# Driver.net
KiCad netlist of a schematic drawn in Altium Designer
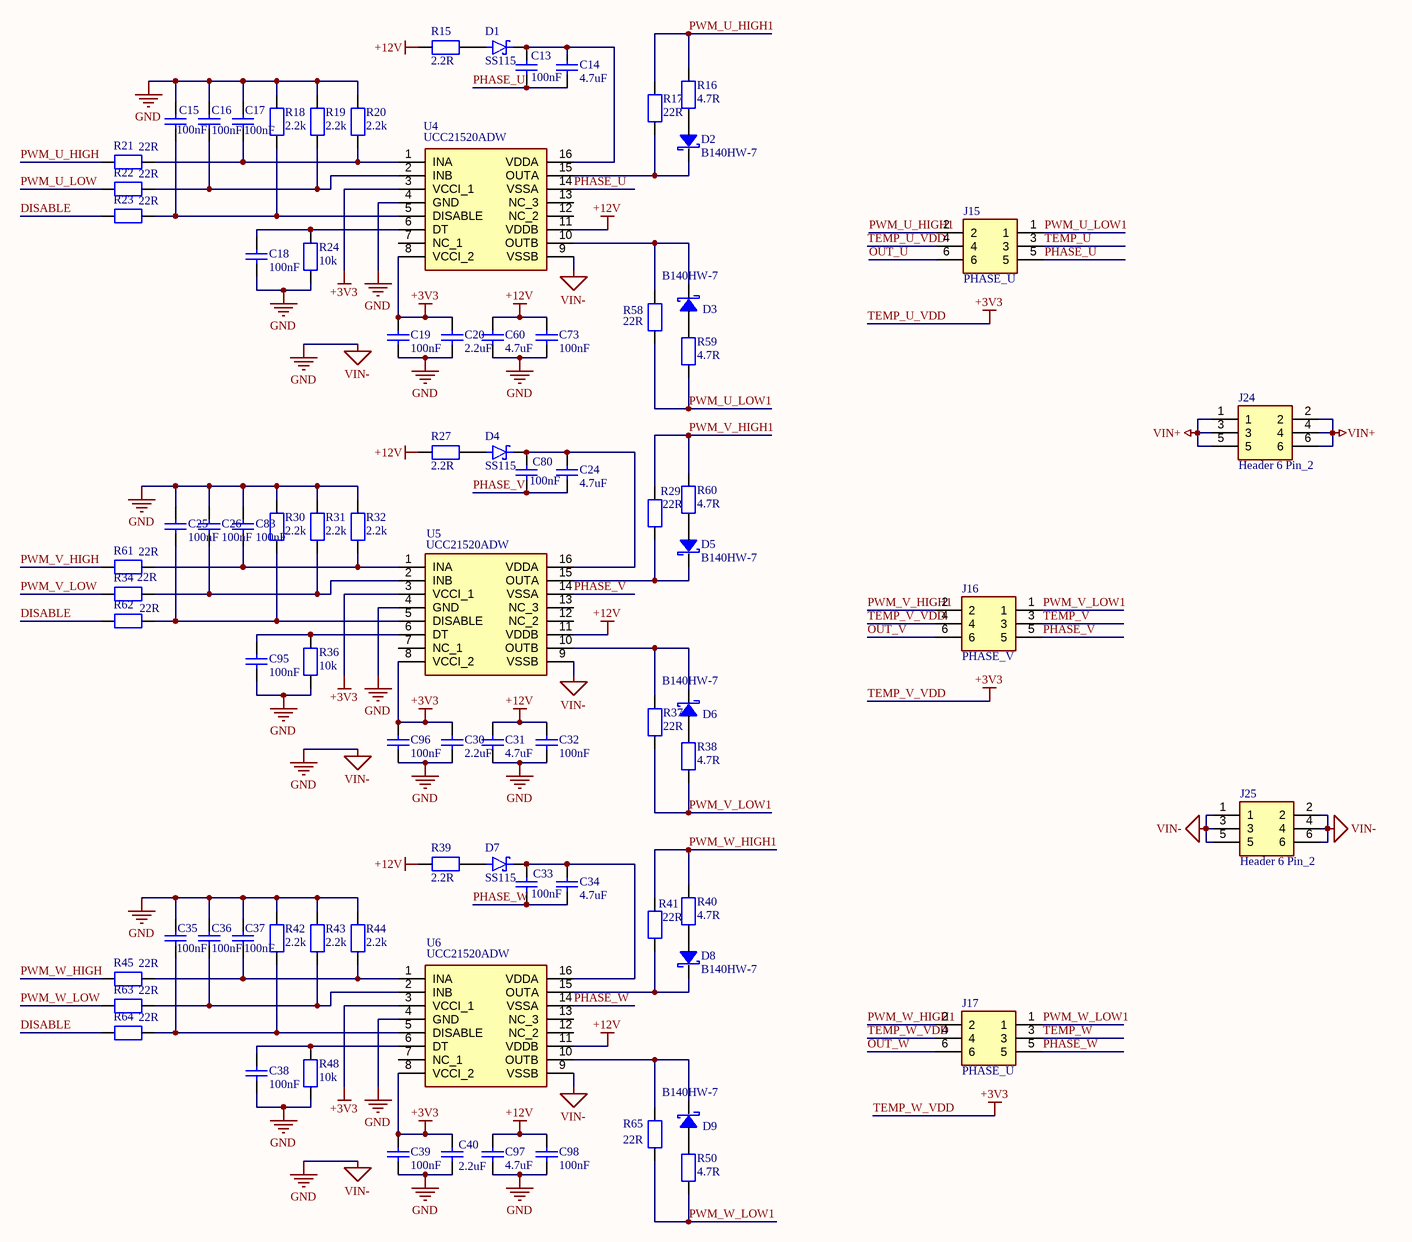
[diagram p0: Driver.SchDoc]

(export (version "E")
  (design (tool "Eeschema 10.0.6"))
  (components
    (comp (ref "C13")
      (value "100nF")
      (footprint "C0603")
      (description "100nF ± 10% 50V")
      (fields
        (field (name "MANUFACTURER") "Yageo")
        (field (name "MANUFACTURER PART NUMBER") "CS0603KRX7R9BB104")
      )
      (libsource (lib "VESC_MotorController") (part "100nF ± 10% 50V"))
    )
    (comp (ref "C14")
      (value "4.7uF")
      (footprint "C0603")
      (description "4.7uF ± 10% 50V")
      (fields
        (field (name "MANUFACTURER") "Yageo")
        (field (name "MANUFACTURER PART NUMBER") "GRM188R61H225ME11J")
      )
      (libsource (lib "VESC_MotorController") (part "4.7uF ± 10% 50V"))
    )
    (comp (ref "C15")
      (value "100nF")
      (footprint "C0603")
      (description "100nF ± 10% 50V")
      (fields
        (field (name "MANUFACTURER") "Yageo")
        (field (name "MANUFACTURER PART NUMBER") "CS0603KRX7R9BB104")
      )
      (libsource (lib "VESC_MotorController") (part "100nF ± 10% 50V"))
    )
    (comp (ref "C16")
      (value "100nF")
      (footprint "C0603")
      (description "100nF ± 10% 50V")
      (fields
        (field (name "MANUFACTURER") "Yageo")
        (field (name "MANUFACTURER PART NUMBER") "CS0603KRX7R9BB104")
      )
      (libsource (lib "VESC_MotorController") (part "100nF ± 10% 50V"))
    )
    (comp (ref "C17")
      (value "100nF")
      (footprint "C0603")
      (description "100nF ± 10% 50V")
      (fields
        (field (name "MANUFACTURER") "Yageo")
        (field (name "MANUFACTURER PART NUMBER") "CS0603KRX7R9BB104")
      )
      (libsource (lib "VESC_MotorController") (part "100nF ± 10% 50V"))
    )
    (comp (ref "C18")
      (value "100nF")
      (footprint "C0603")
      (description "100nF ± 10% 50V")
      (fields
        (field (name "MANUFACTURER") "Yageo")
        (field (name "MANUFACTURER PART NUMBER") "CS0603KRX7R9BB104")
      )
      (libsource (lib "VESC_MotorController") (part "100nF ± 10% 50V"))
    )
    (comp (ref "C19")
      (value "100nF")
      (footprint "C0603")
      (description "100nF ± 10% 50V")
      (fields
        (field (name "MANUFACTURER") "Yageo")
        (field (name "MANUFACTURER PART NUMBER") "CS0603KRX7R9BB104")
      )
      (libsource (lib "VESC_MotorController") (part "100nF ± 10% 50V"))
    )
    (comp (ref "C20")
      (value "2.2uF")
      (footprint "C0603")
      (description "2.2uF ± 10% 50V")
      (fields
        (field (name "MANUFACTURER") "Yageo")
        (field (name "MANUFACTURER PART NUMBER") "GRM188R61H225ME11J")
      )
      (libsource (lib "VESC_MotorController") (part "2.2uF ± 10% 50V"))
    )
    (comp (ref "C24")
      (value "4.7uF")
      (footprint "C0603")
      (description "4.7uF ± 10% 50V")
      (fields
        (field (name "MANUFACTURER") "Yageo")
        (field (name "MANUFACTURER PART NUMBER") "GRM188R61H225ME11J")
      )
      (libsource (lib "VESC_MotorController") (part "4.7uF ± 10% 50V"))
    )
    (comp (ref "C25")
      (value "100nF")
      (footprint "C0603")
      (description "100nF ± 10% 50V")
      (fields
        (field (name "MANUFACTURER") "Yageo")
        (field (name "MANUFACTURER PART NUMBER") "CS0603KRX7R9BB104")
      )
      (libsource (lib "VESC_MotorController") (part "100nF ± 10% 50V"))
    )
    (comp (ref "C26")
      (value "100nF")
      (footprint "C0603")
      (description "100nF ± 10% 50V")
      (fields
        (field (name "MANUFACTURER") "Yageo")
        (field (name "MANUFACTURER PART NUMBER") "CS0603KRX7R9BB104")
      )
      (libsource (lib "VESC_MotorController") (part "100nF ± 10% 50V"))
    )
    (comp (ref "C30")
      (value "2.2uF")
      (footprint "C0603")
      (description "2.2uF ± 10% 50V")
      (fields
        (field (name "MANUFACTURER") "Yageo")
        (field (name "MANUFACTURER PART NUMBER") "GRM188R61H225ME11J")
      )
      (libsource (lib "VESC_MotorController") (part "2.2uF ± 10% 50V"))
    )
    (comp (ref "C31")
      (value "4.7uF")
      (footprint "C0603")
      (description "4.7uF ± 10% 50V")
      (fields
        (field (name "MANUFACTURER") "Yageo")
        (field (name "MANUFACTURER PART NUMBER") "GRM188R61H225ME11J")
      )
      (libsource (lib "VESC_MotorController") (part "4.7uF ± 10% 50V"))
    )
    (comp (ref "C32")
      (value "100nF")
      (footprint "C0603")
      (description "100nF ± 10% 50V")
      (fields
        (field (name "MANUFACTURER") "Yageo")
        (field (name "MANUFACTURER PART NUMBER") "CS0603KRX7R9BB104")
      )
      (libsource (lib "VESC_MotorController") (part "100nF ± 10% 50V"))
    )
    (comp (ref "C33")
      (value "100nF")
      (footprint "C0603")
      (description "100nF ± 10% 50V")
      (fields
        (field (name "MANUFACTURER") "Yageo")
        (field (name "MANUFACTURER PART NUMBER") "CS0603KRX7R9BB104")
      )
      (libsource (lib "VESC_MotorController") (part "100nF ± 10% 50V"))
    )
    (comp (ref "C34")
      (value "4.7uF")
      (footprint "C0603")
      (description "4.7uF ± 10% 50V")
      (fields
        (field (name "MANUFACTURER") "Yageo")
        (field (name "MANUFACTURER PART NUMBER") "GRM188R61H225ME11J")
      )
      (libsource (lib "VESC_MotorController") (part "4.7uF ± 10% 50V"))
    )
    (comp (ref "C35")
      (value "100nF")
      (footprint "C0603")
      (description "100nF ± 10% 50V")
      (fields
        (field (name "MANUFACTURER") "Yageo")
        (field (name "MANUFACTURER PART NUMBER") "CS0603KRX7R9BB104")
      )
      (libsource (lib "VESC_MotorController") (part "100nF ± 10% 50V"))
    )
    (comp (ref "C36")
      (value "100nF")
      (footprint "C0603")
      (description "100nF ± 10% 50V")
      (fields
        (field (name "MANUFACTURER") "Yageo")
        (field (name "MANUFACTURER PART NUMBER") "CS0603KRX7R9BB104")
      )
      (libsource (lib "VESC_MotorController") (part "100nF ± 10% 50V"))
    )
    (comp (ref "C37")
      (value "100nF")
      (footprint "C0603")
      (description "100nF ± 10% 50V")
      (fields
        (field (name "MANUFACTURER") "Yageo")
        (field (name "MANUFACTURER PART NUMBER") "CS0603KRX7R9BB104")
      )
      (libsource (lib "VESC_MotorController") (part "100nF ± 10% 50V"))
    )
    (comp (ref "C38")
      (value "100nF")
      (footprint "C0603")
      (description "100nF ± 10% 50V")
      (fields
        (field (name "MANUFACTURER") "Yageo")
        (field (name "MANUFACTURER PART NUMBER") "CS0603KRX7R9BB104")
      )
      (libsource (lib "VESC_MotorController") (part "100nF ± 10% 50V"))
    )
    (comp (ref "C39")
      (value "100nF")
      (footprint "C0603")
      (description "100nF ± 10% 50V")
      (fields
        (field (name "MANUFACTURER") "Yageo")
        (field (name "MANUFACTURER PART NUMBER") "CS0603KRX7R9BB104")
      )
      (libsource (lib "VESC_MotorController") (part "100nF ± 10% 50V"))
    )
    (comp (ref "C40")
      (value "2.2uF")
      (footprint "C0603")
      (description "2.2uF ± 10% 50V")
      (fields
        (field (name "MANUFACTURER") "Yageo")
        (field (name "MANUFACTURER PART NUMBER") "GRM188R61H225ME11J")
      )
      (libsource (lib "VESC_MotorController") (part "2.2uF ± 10% 50V"))
    )
    (comp (ref "C60")
      (value "4.7uF")
      (footprint "C0603")
      (description "4.7uF ± 10% 50V")
      (fields
        (field (name "MANUFACTURER") "Yageo")
        (field (name "MANUFACTURER PART NUMBER") "GRM188R61H225ME11J")
      )
      (libsource (lib "VESC_MotorController") (part "4.7uF ± 10% 50V"))
    )
    (comp (ref "C73")
      (value "100nF")
      (footprint "C0603")
      (description "100nF ± 10% 50V")
      (fields
        (field (name "MANUFACTURER") "Yageo")
        (field (name "MANUFACTURER PART NUMBER") "CS0603KRX7R9BB104")
      )
      (libsource (lib "VESC_MotorController") (part "100nF ± 10% 50V"))
    )
    (comp (ref "C80")
      (value "100nF")
      (footprint "C0603")
      (description "100nF ± 10% 50V")
      (fields
        (field (name "MANUFACTURER") "Yageo")
        (field (name "MANUFACTURER PART NUMBER") "CS0603KRX7R9BB104")
      )
      (libsource (lib "VESC_MotorController") (part "100nF ± 10% 50V"))
    )
    (comp (ref "C83")
      (value "100nF")
      (footprint "C0603")
      (description "100nF ± 10% 50V")
      (fields
        (field (name "MANUFACTURER") "Yageo")
        (field (name "MANUFACTURER PART NUMBER") "CS0603KRX7R9BB104")
      )
      (libsource (lib "VESC_MotorController") (part "100nF ± 10% 50V"))
    )
    (comp (ref "C95")
      (value "100nF")
      (footprint "C0603")
      (description "100nF ± 10% 50V")
      (fields
        (field (name "MANUFACTURER") "Yageo")
        (field (name "MANUFACTURER PART NUMBER") "CS0603KRX7R9BB104")
      )
      (libsource (lib "VESC_MotorController") (part "100nF ± 10% 50V"))
    )
    (comp (ref "C96")
      (value "100nF")
      (footprint "C0603")
      (description "100nF ± 10% 50V")
      (fields
        (field (name "MANUFACTURER") "Yageo")
        (field (name "MANUFACTURER PART NUMBER") "CS0603KRX7R9BB104")
      )
      (libsource (lib "VESC_MotorController") (part "100nF ± 10% 50V"))
    )
    (comp (ref "C97")
      (value "4.7uF")
      (footprint "C0603")
      (description "4.7uF ± 10% 50V")
      (fields
        (field (name "MANUFACTURER") "Yageo")
        (field (name "MANUFACTURER PART NUMBER") "GRM188R61H225ME11J")
      )
      (libsource (lib "VESC_MotorController") (part "4.7uF ± 10% 50V"))
    )
    (comp (ref "C98")
      (value "100nF")
      (footprint "C0603")
      (description "100nF ± 10% 50V")
      (fields
        (field (name "MANUFACTURER") "Yageo")
        (field (name "MANUFACTURER PART NUMBER") "CS0603KRX7R9BB104")
      )
      (libsource (lib "VESC_MotorController") (part "100nF ± 10% 50V"))
    )
    (comp (ref "D1")
      (value "SS115")
      (footprint "DIOM4325X250N")
      (description "Schottky Diodes & Rectifiers 1A, 150V, Schottky Rectifier")
      (fields (field (name "MANUFACTURER") "Taiwan Semiconductor"))
      (libsource (lib "VESC_MotorController") (part "SS115"))
    )
    (comp (ref "D2")
      (value "B140HW-7")
      (footprint "SOD123")
      (description "Schottky Diodes & Rectifiers 1A, 40V")
      (fields (field (name "MANUFACTURER") "Diodes"))
      (libsource (lib "VESC_MotorController") (part "B140HW-7"))
    )
    (comp (ref "D3")
      (value "B140HW-7")
      (footprint "SOD123")
      (description "Schottky Diodes & Rectifiers 1A, 40V")
      (fields (field (name "MANUFACTURER") "Diodes"))
      (libsource (lib "VESC_MotorController") (part "B140HW-7"))
    )
    (comp (ref "D4")
      (value "SS115")
      (footprint "DIOM4325X250N")
      (description "Schottky Diodes & Rectifiers 1A, 150V, Schottky Rectifier")
      (fields (field (name "MANUFACTURER") "Taiwan Semiconductor"))
      (libsource (lib "VESC_MotorController") (part "SS115"))
    )
    (comp (ref "D5")
      (value "B140HW-7")
      (footprint "SOD123")
      (description "Schottky Diodes & Rectifiers 1A, 40V")
      (fields (field (name "MANUFACTURER") "Diodes"))
      (libsource (lib "VESC_MotorController") (part "B140HW-7"))
    )
    (comp (ref "D6")
      (value "B140HW-7")
      (footprint "SOD123")
      (description "Schottky Diodes & Rectifiers 1A, 40V")
      (fields (field (name "MANUFACTURER") "Diodes"))
      (libsource (lib "VESC_MotorController") (part "B140HW-7"))
    )
    (comp (ref "D7")
      (value "SS115")
      (footprint "DIOM4325X250N")
      (description "Schottky Diodes & Rectifiers 1A, 150V, Schottky Rectifier")
      (fields (field (name "MANUFACTURER") "Taiwan Semiconductor"))
      (libsource (lib "VESC_MotorController") (part "SS115"))
    )
    (comp (ref "D8")
      (value "B140HW-7")
      (footprint "SOD123")
      (description "Schottky Diodes & Rectifiers 1A, 40V")
      (fields (field (name "MANUFACTURER") "Diodes"))
      (libsource (lib "VESC_MotorController") (part "B140HW-7"))
    )
    (comp (ref "D9")
      (value "B140HW-7")
      (footprint "SOD123")
      (description "Schottky Diodes & Rectifiers 1A, 40V")
      (fields (field (name "MANUFACTURER") "Diodes"))
      (libsource (lib "VESC_MotorController") (part "B140HW-7"))
    )
    (comp (ref "J15")
      (value "PHASE_U")
      (footprint "61300621121")
      (fields
        (field (name "MANUFACTURER") "Wurth Elektronik")
        (field (name "MANUFACTURER PART NUMBER") "61300621121")
      )
      (libsource (lib "") (part "Header 6 Pin_2_1"))
    )
    (comp (ref "J16")
      (value "PHASE_V")
      (footprint "61300621121")
      (fields
        (field (name "MANUFACTURER") "Wurth Elektronik")
        (field (name "MANUFACTURER PART NUMBER") "61300621121")
      )
      (libsource (lib "") (part "Header 6 Pin_2_1"))
    )
    (comp (ref "J17")
      (value "PHASE_U")
      (footprint "61300621121")
      (fields
        (field (name "MANUFACTURER") "Wurth Elektronik")
        (field (name "MANUFACTURER PART NUMBER") "61300621121")
      )
      (libsource (lib "") (part "Header 6 Pin_2_1"))
    )
    (comp (ref "J24")
      (value "Header 6 Pin_2")
      (footprint "61300621121")
      (fields
        (field (name "MANUFACTURER") "Wurth Elektronik")
        (field (name "MANUFACTURER PART NUMBER") "61300621121")
      )
      (libsource (lib "VESC_MotorController") (part "Header 6 Pin_2"))
    )
    (comp (ref "J25")
      (value "Header 6 Pin_2")
      (footprint "61300621121")
      (fields
        (field (name "MANUFACTURER") "Wurth Elektronik")
        (field (name "MANUFACTURER PART NUMBER") "61300621121")
      )
      (libsource (lib "VESC_MotorController") (part "Header 6 Pin_2"))
    )
    (comp (ref "R15")
      (value "2.2R")
      (footprint "R0603")
      (description "2.2 ohm 0.1W ±1%")
      (fields
        (field (name "MANUFACTURER PART NUMBER") "RC0603FR-072R2L")
        (field (name "MANUFACTURER") "Yageo")
      )
      (libsource (lib "VESC_MotorController") (part "2.2ohm 0.1W ±1%"))
    )
    (comp (ref "R16")
      (value "4.7R")
      (footprint "R0603")
      (description "4.7 ohm 0.1W ±1%")
      (fields
        (field (name "MANUFACTURER PART NUMBER") "RC1206FR-074R7L")
        (field (name "MANUFACTURER") "Yageo")
      )
      (libsource (lib "VESC_MotorController") (part "4.7ohm 0.1W ±10%"))
    )
    (comp (ref "R17")
      (value "22R")
      (footprint "R0603")
      (description "22 ohm 0.1W ±1%")
      (fields
        (field (name "MANUFACTURER PART NUMBER") "RC0603FR-0722RL")
        (field (name "MANUFACTURER") "Yageo")
      )
      (libsource (lib "VESC_MotorController") (part "22ohm 0.1W ±1%"))
    )
    (comp (ref "R18")
      (value "2.2k")
      (footprint "R0603")
      (description "2.2 kOhms ±1% 0.1W")
      (fields
        (field (name "MANUFACTURER") "Yageo")
        (field (name "MANUFACTURER PART NUMBER") "RC0603FR-072K2L")
      )
      (libsource (lib "VESC_MotorController") (part "2.2 kOhms ±1% 0.1W"))
    )
    (comp (ref "R19")
      (value "2.2k")
      (footprint "R0603")
      (description "2.2 kOhms ±1% 0.1W")
      (fields
        (field (name "MANUFACTURER") "Yageo")
        (field (name "MANUFACTURER PART NUMBER") "RC0603FR-072K2L")
      )
      (libsource (lib "VESC_MotorController") (part "2.2 kOhms ±1% 0.1W"))
    )
    (comp (ref "R20")
      (value "2.2k")
      (footprint "R0603")
      (description "2.2 kOhms ±1% 0.1W")
      (fields
        (field (name "MANUFACTURER") "Yageo")
        (field (name "MANUFACTURER PART NUMBER") "RC0603FR-072K2L")
      )
      (libsource (lib "VESC_MotorController") (part "2.2 kOhms ±1% 0.1W"))
    )
    (comp (ref "R21")
      (value "22R")
      (footprint "R0603")
      (description "22 ohm 0.1W ±1%")
      (fields
        (field (name "MANUFACTURER PART NUMBER") "RC0603FR-0722RL")
        (field (name "MANUFACTURER") "Yageo")
      )
      (libsource (lib "VESC_MotorController") (part "22ohm 0.1W ±1%"))
    )
    (comp (ref "R22")
      (value "22R")
      (footprint "R0603")
      (description "22 ohm 0.1W ±1%")
      (fields
        (field (name "MANUFACTURER PART NUMBER") "RC0603FR-0722RL")
        (field (name "MANUFACTURER") "Yageo")
      )
      (libsource (lib "VESC_MotorController") (part "22ohm 0.1W ±1%"))
    )
    (comp (ref "R23")
      (value "22R")
      (footprint "R0603")
      (description "22 ohm 0.1W ±1%")
      (fields
        (field (name "MANUFACTURER PART NUMBER") "RC0603FR-0722RL")
        (field (name "MANUFACTURER") "Yageo")
      )
      (libsource (lib "VESC_MotorController") (part "22ohm 0.1W ±1%"))
    )
    (comp (ref "R24")
      (value "10k")
      (footprint "R0603")
      (description "10 kOhms ±1% 0.1W")
      (fields
        (field (name "MANUFACTURER") "Yageo")
        (field (name "MANUFACTURER PART NUMBER") "RC0603FR-0710KL")
      )
      (libsource (lib "VESC_MotorController") (part "10 kOhms ±1% 0.1W"))
    )
    (comp (ref "R27")
      (value "2.2R")
      (footprint "R0603")
      (description "2.2 ohm 0.1W ±1%")
      (fields
        (field (name "MANUFACTURER PART NUMBER") "RC0603FR-072R2L")
        (field (name "MANUFACTURER") "Yageo")
      )
      (libsource (lib "VESC_MotorController") (part "2.2ohm 0.1W ±1%"))
    )
    (comp (ref "R29")
      (value "22R")
      (footprint "R0603")
      (description "22 ohm 0.1W ±1%")
      (fields
        (field (name "MANUFACTURER PART NUMBER") "RC0603FR-0722RL")
        (field (name "MANUFACTURER") "Yageo")
      )
      (libsource (lib "VESC_MotorController") (part "22ohm 0.1W ±1%"))
    )
    (comp (ref "R30")
      (value "2.2k")
      (footprint "R0603")
      (description "2.2 kOhms ±1% 0.1W")
      (fields
        (field (name "MANUFACTURER") "Yageo")
        (field (name "MANUFACTURER PART NUMBER") "RC0603FR-072K2L")
      )
      (libsource (lib "VESC_MotorController") (part "2.2 kOhms ±1% 0.1W"))
    )
    (comp (ref "R31")
      (value "2.2k")
      (footprint "R0603")
      (description "2.2 kOhms ±1% 0.1W")
      (fields
        (field (name "MANUFACTURER") "Yageo")
        (field (name "MANUFACTURER PART NUMBER") "RC0603FR-072K2L")
      )
      (libsource (lib "VESC_MotorController") (part "2.2 kOhms ±1% 0.1W"))
    )
    (comp (ref "R32")
      (value "2.2k")
      (footprint "R0603")
      (description "2.2 kOhms ±1% 0.1W")
      (fields
        (field (name "MANUFACTURER") "Yageo")
        (field (name "MANUFACTURER PART NUMBER") "RC0603FR-072K2L")
      )
      (libsource (lib "VESC_MotorController") (part "2.2 kOhms ±1% 0.1W"))
    )
    (comp (ref "R34")
      (value "22R")
      (footprint "R0603")
      (description "22 ohm 0.1W ±1%")
      (fields
        (field (name "MANUFACTURER PART NUMBER") "RC0603FR-0722RL")
        (field (name "MANUFACTURER") "Yageo")
      )
      (libsource (lib "VESC_MotorController") (part "22ohm 0.1W ±1%"))
    )
    (comp (ref "R36")
      (value "10k")
      (footprint "R0603")
      (description "10 kOhms ±1% 0.1W")
      (fields
        (field (name "MANUFACTURER") "Yageo")
        (field (name "MANUFACTURER PART NUMBER") "RC0603FR-0710KL")
      )
      (libsource (lib "VESC_MotorController") (part "10 kOhms ±1% 0.1W"))
    )
    (comp (ref "R37")
      (value "22R")
      (footprint "R0603")
      (description "22 ohm 0.1W ±1%")
      (fields
        (field (name "MANUFACTURER PART NUMBER") "RC0603FR-0722RL")
        (field (name "MANUFACTURER") "Yageo")
      )
      (libsource (lib "VESC_MotorController") (part "22ohm 0.1W ±1%"))
    )
    (comp (ref "R38")
      (value "4.7R")
      (footprint "R0603")
      (description "4.7 ohm 0.1W ±1%")
      (fields
        (field (name "MANUFACTURER PART NUMBER") "RC1206FR-074R7L")
        (field (name "MANUFACTURER") "Yageo")
      )
      (libsource (lib "VESC_MotorController") (part "4.7ohm 0.1W ±10%"))
    )
    (comp (ref "R39")
      (value "2.2R")
      (footprint "R0603")
      (description "2.2 ohm 0.1W ±1%")
      (fields
        (field (name "MANUFACTURER PART NUMBER") "RC0603FR-072R2L")
        (field (name "MANUFACTURER") "Yageo")
      )
      (libsource (lib "VESC_MotorController") (part "2.2ohm 0.1W ±1%"))
    )
    (comp (ref "R40")
      (value "4.7R")
      (footprint "R0603")
      (description "4.7 ohm 0.1W ±1%")
      (fields
        (field (name "MANUFACTURER PART NUMBER") "RC1206FR-074R7L")
        (field (name "MANUFACTURER") "Yageo")
      )
      (libsource (lib "VESC_MotorController") (part "4.7ohm 0.1W ±10%"))
    )
    (comp (ref "R41")
      (value "22R")
      (footprint "R0603")
      (description "22 ohm 0.1W ±1%")
      (fields
        (field (name "MANUFACTURER PART NUMBER") "RC0603FR-0722RL")
        (field (name "MANUFACTURER") "Yageo")
      )
      (libsource (lib "VESC_MotorController") (part "22ohm 0.1W ±1%"))
    )
    (comp (ref "R42")
      (value "2.2k")
      (footprint "R0603")
      (description "2.2 kOhms ±1% 0.1W")
      (fields
        (field (name "MANUFACTURER") "Yageo")
        (field (name "MANUFACTURER PART NUMBER") "RC0603FR-072K2L")
      )
      (libsource (lib "VESC_MotorController") (part "2.2 kOhms ±1% 0.1W"))
    )
    (comp (ref "R43")
      (value "2.2k")
      (footprint "R0603")
      (description "2.2 kOhms ±1% 0.1W")
      (fields
        (field (name "MANUFACTURER") "Yageo")
        (field (name "MANUFACTURER PART NUMBER") "RC0603FR-072K2L")
      )
      (libsource (lib "VESC_MotorController") (part "2.2 kOhms ±1% 0.1W"))
    )
    (comp (ref "R44")
      (value "2.2k")
      (footprint "R0603")
      (description "2.2 kOhms ±1% 0.1W")
      (fields
        (field (name "MANUFACTURER") "Yageo")
        (field (name "MANUFACTURER PART NUMBER") "RC0603FR-072K2L")
      )
      (libsource (lib "VESC_MotorController") (part "2.2 kOhms ±1% 0.1W"))
    )
    (comp (ref "R45")
      (value "22R")
      (footprint "R0603")
      (description "22 ohm 0.1W ±1%")
      (fields
        (field (name "MANUFACTURER PART NUMBER") "RC0603FR-0722RL")
        (field (name "MANUFACTURER") "Yageo")
      )
      (libsource (lib "VESC_MotorController") (part "22ohm 0.1W ±1%"))
    )
    (comp (ref "R48")
      (value "10k")
      (footprint "R0603")
      (description "10 kOhms ±1% 0.1W")
      (fields
        (field (name "MANUFACTURER") "Yageo")
        (field (name "MANUFACTURER PART NUMBER") "RC0603FR-0710KL")
      )
      (libsource (lib "VESC_MotorController") (part "10 kOhms ±1% 0.1W"))
    )
    (comp (ref "R50")
      (value "4.7R")
      (footprint "R0603")
      (description "4.7 ohm 0.1W ±1%")
      (fields
        (field (name "MANUFACTURER PART NUMBER") "RC1206FR-074R7L")
        (field (name "MANUFACTURER") "Yageo")
      )
      (libsource (lib "VESC_MotorController") (part "4.7ohm 0.1W ±10%"))
    )
    (comp (ref "R58")
      (value "22R")
      (footprint "R0603")
      (description "22 ohm 0.1W ±1%")
      (fields
        (field (name "MANUFACTURER PART NUMBER") "RC0603FR-0722RL")
        (field (name "MANUFACTURER") "Yageo")
      )
      (libsource (lib "VESC_MotorController") (part "22ohm 0.1W ±1%"))
    )
    (comp (ref "R59")
      (value "4.7R")
      (footprint "R0603")
      (description "4.7 ohm 0.1W ±1%")
      (fields
        (field (name "MANUFACTURER PART NUMBER") "RC1206FR-074R7L")
        (field (name "MANUFACTURER") "Yageo")
      )
      (libsource (lib "VESC_MotorController") (part "4.7ohm 0.1W ±10%"))
    )
    (comp (ref "R60")
      (value "4.7R")
      (footprint "R0603")
      (description "4.7 ohm 0.1W ±1%")
      (fields
        (field (name "MANUFACTURER PART NUMBER") "RC1206FR-074R7L")
        (field (name "MANUFACTURER") "Yageo")
      )
      (libsource (lib "VESC_MotorController") (part "4.7ohm 0.1W ±10%"))
    )
    (comp (ref "R61")
      (value "22R")
      (footprint "R0603")
      (description "22 ohm 0.1W ±1%")
      (fields
        (field (name "MANUFACTURER PART NUMBER") "RC0603FR-0722RL")
        (field (name "MANUFACTURER") "Yageo")
      )
      (libsource (lib "VESC_MotorController") (part "22ohm 0.1W ±1%"))
    )
    (comp (ref "R62")
      (value "22R")
      (footprint "R0603")
      (description "22 ohm 0.1W ±1%")
      (fields
        (field (name "MANUFACTURER PART NUMBER") "RC0603FR-0722RL")
        (field (name "MANUFACTURER") "Yageo")
      )
      (libsource (lib "VESC_MotorController") (part "22ohm 0.1W ±1%"))
    )
    (comp (ref "R63")
      (value "22R")
      (footprint "R0603")
      (description "22 ohm 0.1W ±1%")
      (fields
        (field (name "MANUFACTURER PART NUMBER") "RC0603FR-0722RL")
        (field (name "MANUFACTURER") "Yageo")
      )
      (libsource (lib "VESC_MotorController") (part "22ohm 0.1W ±1%"))
    )
    (comp (ref "R64")
      (value "22R")
      (footprint "R0603")
      (description "22 ohm 0.1W ±1%")
      (fields
        (field (name "MANUFACTURER PART NUMBER") "RC0603FR-0722RL")
        (field (name "MANUFACTURER") "Yageo")
      )
      (libsource (lib "VESC_MotorController") (part "22ohm 0.1W ±1%"))
    )
    (comp (ref "R65")
      (value "22R")
      (footprint "R0603")
      (description "22 ohm 0.1W ±1%")
      (fields
        (field (name "MANUFACTURER PART NUMBER") "RC0603FR-0722RL")
        (field (name "MANUFACTURER") "Yageo")
      )
      (libsource (lib "VESC_MotorController") (part "22ohm 0.1W ±1%"))
    )
    (comp (ref "U4")
      (value "UCC21520ADW")
      (footprint "SOIC127P1030X265-16N")
      (description "4A/6A, 5.7 kVrms Isolated Dual Channel Gate Driver")
      (fields (field (name "MANUFACTURER") "Texas Instruments"))
      (libsource (lib "VESC_MotorController") (part "UCC21520ADW"))
    )
    (comp (ref "U5")
      (value "UCC21520ADW")
      (footprint "SOIC127P1030X265-16N")
      (description "4A/6A, 5.7 kVrms Isolated Dual Channel Gate Driver")
      (fields (field (name "MANUFACTURER") "Texas Instruments"))
      (libsource (lib "VESC_MotorController") (part "UCC21520ADW"))
    )
    (comp (ref "U6")
      (value "UCC21520ADW")
      (footprint "SOIC127P1030X265-16N")
      (description "4A/6A, 5.7 kVrms Isolated Dual Channel Gate Driver")
      (fields (field (name "MANUFACTURER") "Texas Instruments"))
      (libsource (lib "VESC_MotorController") (part "UCC21520ADW"))
    )
  )
  (nets
    (net (code "1") (name "+3V3") (class "Default")
      (node (ref "C19") (pin "2") (pinfunction "2_2") (pintype "passive"))
      (node (ref "C20") (pin "2") (pinfunction "2_2") (pintype "passive"))
      (node (ref "C30") (pin "2") (pinfunction "2_2") (pintype "passive"))
      (node (ref "C39") (pin "2") (pinfunction "2_2") (pintype "passive"))
      (node (ref "C40") (pin "2") (pinfunction "2_2") (pintype "passive"))
      (node (ref "C96") (pin "2") (pinfunction "2_2") (pintype "passive"))
      (node (ref "J15") (pin "4") (pinfunction "4_4") (pintype "passive"))
      (node (ref "J16") (pin "4") (pinfunction "4_4") (pintype "passive"))
      (node (ref "J17") (pin "4") (pinfunction "4_4") (pintype "passive"))
      (node (ref "U4") (pin "3") (pinfunction "VCCI_1_3") (pintype "passive"))
      (node (ref "U4") (pin "8") (pinfunction "VCCI_2_8") (pintype "passive"))
      (node (ref "U5") (pin "3") (pinfunction "VCCI_1_3") (pintype "passive"))
      (node (ref "U5") (pin "8") (pinfunction "VCCI_2_8") (pintype "passive"))
      (node (ref "U6") (pin "3") (pinfunction "VCCI_1_3") (pintype "passive"))
      (node (ref "U6") (pin "8") (pinfunction "VCCI_2_8") (pintype "passive"))
    )
    (net (code "2") (name "+12V") (class "Default")
      (node (ref "C31") (pin "2") (pinfunction "2_2") (pintype "passive"))
      (node (ref "C32") (pin "2") (pinfunction "2_2") (pintype "passive"))
      (node (ref "C60") (pin "2") (pinfunction "2_2") (pintype "passive"))
      (node (ref "C73") (pin "2") (pinfunction "2_2") (pintype "passive"))
      (node (ref "C97") (pin "2") (pinfunction "2_2") (pintype "passive"))
      (node (ref "C98") (pin "2") (pinfunction "2_2") (pintype "passive"))
      (node (ref "R15") (pin "1") (pinfunction "1_1") (pintype "passive"))
      (node (ref "R27") (pin "1") (pinfunction "1_1") (pintype "passive"))
      (node (ref "R39") (pin "1") (pinfunction "1_1") (pintype "passive"))
      (node (ref "U4") (pin "11") (pinfunction "VDDB_11") (pintype "passive"))
      (node (ref "U5") (pin "11") (pinfunction "VDDB_11") (pintype "passive"))
      (node (ref "U6") (pin "11") (pinfunction "VDDB_11") (pintype "passive"))
    )
    (net (code "3") (name "/DISABLE") (class "Default")
      (node (ref "R23") (pin "1") (pinfunction "1_1") (pintype "passive"))
      (node (ref "R62") (pin "1") (pinfunction "1_1") (pintype "passive"))
      (node (ref "R64") (pin "1") (pinfunction "1_1") (pintype "passive"))
    )
    (net (code "4") (name "/OUT_U") (class "Default")
      (node (ref "J15") (pin "6") (pinfunction "6_6") (pintype "passive"))
    )
    (net (code "5") (name "/OUT_V") (class "Default")
      (node (ref "J16") (pin "6") (pinfunction "6_6") (pintype "passive"))
    )
    (net (code "6") (name "/OUT_W") (class "Default")
      (node (ref "J17") (pin "6") (pinfunction "6_6") (pintype "passive"))
    )
    (net (code "7") (name "/PHASE_U") (class "Default")
      (node (ref "C13") (pin "1") (pinfunction "1_1") (pintype "passive"))
      (node (ref "C14") (pin "1") (pinfunction "1_1") (pintype "passive"))
      (node (ref "J15") (pin "5") (pinfunction "5_5") (pintype "passive"))
      (node (ref "U4") (pin "14") (pinfunction "VSSA_14") (pintype "passive"))
    )
    (net (code "8") (name "/PHASE_V") (class "Default")
      (node (ref "C24") (pin "1") (pinfunction "1_1") (pintype "passive"))
      (node (ref "C80") (pin "1") (pinfunction "1_1") (pintype "passive"))
      (node (ref "J16") (pin "5") (pinfunction "5_5") (pintype "passive"))
      (node (ref "U5") (pin "14") (pinfunction "VSSA_14") (pintype "passive"))
    )
    (net (code "9") (name "/PHASE_W") (class "Default")
      (node (ref "C33") (pin "1") (pinfunction "1_1") (pintype "passive"))
      (node (ref "C34") (pin "1") (pinfunction "1_1") (pintype "passive"))
      (node (ref "J17") (pin "5") (pinfunction "5_5") (pintype "passive"))
      (node (ref "U6") (pin "14") (pinfunction "VSSA_14") (pintype "passive"))
    )
    (net (code "10") (name "/PWM_U_HIGH") (class "Default")
      (node (ref "R21") (pin "1") (pinfunction "1_1") (pintype "passive"))
    )
    (net (code "11") (name "/PWM_U_HIGH1") (class "Default")
      (node (ref "J15") (pin "2") (pinfunction "2_2") (pintype "passive"))
      (node (ref "R16") (pin "2") (pinfunction "2_2") (pintype "passive"))
      (node (ref "R17") (pin "2") (pinfunction "2_2") (pintype "passive"))
    )
    (net (code "12") (name "/PWM_U_LOW") (class "Default")
      (node (ref "R22") (pin "1") (pinfunction "1_1") (pintype "passive"))
    )
    (net (code "13") (name "/PWM_U_LOW1") (class "Default")
      (node (ref "J15") (pin "1") (pinfunction "1_1") (pintype "passive"))
      (node (ref "R58") (pin "1") (pinfunction "1_1") (pintype "passive"))
      (node (ref "R59") (pin "1") (pinfunction "1_1") (pintype "passive"))
    )
    (net (code "14") (name "/PWM_V_HIGH") (class "Default")
      (node (ref "R61") (pin "1") (pinfunction "1_1") (pintype "passive"))
    )
    (net (code "15") (name "/PWM_V_HIGH1") (class "Default")
      (node (ref "J16") (pin "2") (pinfunction "2_2") (pintype "passive"))
      (node (ref "R29") (pin "2") (pinfunction "2_2") (pintype "passive"))
      (node (ref "R60") (pin "2") (pinfunction "2_2") (pintype "passive"))
    )
    (net (code "16") (name "/PWM_V_LOW") (class "Default")
      (node (ref "R34") (pin "1") (pinfunction "1_1") (pintype "passive"))
    )
    (net (code "17") (name "/PWM_V_LOW1") (class "Default")
      (node (ref "J16") (pin "1") (pinfunction "1_1") (pintype "passive"))
      (node (ref "R37") (pin "1") (pinfunction "1_1") (pintype "passive"))
      (node (ref "R38") (pin "1") (pinfunction "1_1") (pintype "passive"))
    )
    (net (code "18") (name "/PWM_W_HIGH") (class "Default")
      (node (ref "R45") (pin "1") (pinfunction "1_1") (pintype "passive"))
    )
    (net (code "19") (name "/PWM_W_HIGH1") (class "Default")
      (node (ref "J17") (pin "2") (pinfunction "2_2") (pintype "passive"))
      (node (ref "R40") (pin "2") (pinfunction "2_2") (pintype "passive"))
      (node (ref "R41") (pin "2") (pinfunction "2_2") (pintype "passive"))
    )
    (net (code "20") (name "/PWM_W_LOW") (class "Default")
      (node (ref "R63") (pin "1") (pinfunction "1_1") (pintype "passive"))
    )
    (net (code "21") (name "/PWM_W_LOW1") (class "Default")
      (node (ref "J17") (pin "1") (pinfunction "1_1") (pintype "passive"))
      (node (ref "R50") (pin "1") (pinfunction "1_1") (pintype "passive"))
      (node (ref "R65") (pin "1") (pinfunction "1_1") (pintype "passive"))
    )
    (net (code "22") (name "/TEMP_U") (class "Default")
      (node (ref "J15") (pin "3") (pinfunction "3_3") (pintype "passive"))
    )
    (net (code "23") (name "/TEMP_V") (class "Default")
      (node (ref "J16") (pin "3") (pinfunction "3_3") (pintype "passive"))
    )
    (net (code "24") (name "/TEMP_W") (class "Default")
      (node (ref "J17") (pin "3") (pinfunction "3_3") (pintype "passive"))
    )
    (net (code "25") (name "GND") (class "Default")
      (node (ref "C15") (pin "2") (pinfunction "2_2") (pintype "passive"))
      (node (ref "C16") (pin "2") (pinfunction "2_2") (pintype "passive"))
      (node (ref "C17") (pin "2") (pinfunction "2_2") (pintype "passive"))
      (node (ref "C18") (pin "1") (pinfunction "1_1") (pintype "passive"))
      (node (ref "C19") (pin "1") (pinfunction "1_1") (pintype "passive"))
      (node (ref "C20") (pin "1") (pinfunction "1_1") (pintype "passive"))
      (node (ref "C25") (pin "2") (pinfunction "2_2") (pintype "passive"))
      (node (ref "C26") (pin "2") (pinfunction "2_2") (pintype "passive"))
      (node (ref "C30") (pin "1") (pinfunction "1_1") (pintype "passive"))
      (node (ref "C31") (pin "1") (pinfunction "1_1") (pintype "passive"))
      (node (ref "C32") (pin "1") (pinfunction "1_1") (pintype "passive"))
      (node (ref "C35") (pin "2") (pinfunction "2_2") (pintype "passive"))
      (node (ref "C36") (pin "2") (pinfunction "2_2") (pintype "passive"))
      (node (ref "C37") (pin "2") (pinfunction "2_2") (pintype "passive"))
      (node (ref "C38") (pin "1") (pinfunction "1_1") (pintype "passive"))
      (node (ref "C39") (pin "1") (pinfunction "1_1") (pintype "passive"))
      (node (ref "C40") (pin "1") (pinfunction "1_1") (pintype "passive"))
      (node (ref "C60") (pin "1") (pinfunction "1_1") (pintype "passive"))
      (node (ref "C73") (pin "1") (pinfunction "1_1") (pintype "passive"))
      (node (ref "C83") (pin "2") (pinfunction "2_2") (pintype "passive"))
      (node (ref "C95") (pin "1") (pinfunction "1_1") (pintype "passive"))
      (node (ref "C96") (pin "1") (pinfunction "1_1") (pintype "passive"))
      (node (ref "C97") (pin "1") (pinfunction "1_1") (pintype "passive"))
      (node (ref "C98") (pin "1") (pinfunction "1_1") (pintype "passive"))
      (node (ref "J25") (pin "1") (pinfunction "1_1") (pintype "passive"))
      (node (ref "J25") (pin "2") (pinfunction "2_2") (pintype "passive"))
      (node (ref "J25") (pin "3") (pinfunction "3_3") (pintype "passive"))
      (node (ref "J25") (pin "4") (pinfunction "4_4") (pintype "passive"))
      (node (ref "J25") (pin "5") (pinfunction "5_5") (pintype "passive"))
      (node (ref "J25") (pin "6") (pinfunction "6_6") (pintype "passive"))
      (node (ref "R18") (pin "2") (pinfunction "2_2") (pintype "passive"))
      (node (ref "R19") (pin "2") (pinfunction "2_2") (pintype "passive"))
      (node (ref "R20") (pin "2") (pinfunction "2_2") (pintype "passive"))
      (node (ref "R24") (pin "1") (pinfunction "1_1") (pintype "passive"))
      (node (ref "R30") (pin "2") (pinfunction "2_2") (pintype "passive"))
      (node (ref "R31") (pin "2") (pinfunction "2_2") (pintype "passive"))
      (node (ref "R32") (pin "2") (pinfunction "2_2") (pintype "passive"))
      (node (ref "R36") (pin "1") (pinfunction "1_1") (pintype "passive"))
      (node (ref "R42") (pin "2") (pinfunction "2_2") (pintype "passive"))
      (node (ref "R43") (pin "2") (pinfunction "2_2") (pintype "passive"))
      (node (ref "R44") (pin "2") (pinfunction "2_2") (pintype "passive"))
      (node (ref "R48") (pin "1") (pinfunction "1_1") (pintype "passive"))
      (node (ref "U4") (pin "4") (pinfunction "GND_4") (pintype "passive"))
      (node (ref "U4") (pin "9") (pinfunction "VSSB_9") (pintype "passive"))
      (node (ref "U5") (pin "4") (pinfunction "GND_4") (pintype "passive"))
      (node (ref "U5") (pin "9") (pinfunction "VSSB_9") (pintype "passive"))
      (node (ref "U6") (pin "4") (pinfunction "GND_4") (pintype "passive"))
      (node (ref "U6") (pin "9") (pinfunction "VSSB_9") (pintype "passive"))
    )
    (net (code "26") (name "Net-(D1-K)") (class "Default")
      (node (ref "C13") (pin "2") (pinfunction "2_2") (pintype "passive"))
      (node (ref "C14") (pin "2") (pinfunction "2_2") (pintype "passive"))
      (node (ref "D1") (pin "C") (pinfunction "K_C") (pintype "passive"))
      (node (ref "U4") (pin "16") (pinfunction "VDDA_16") (pintype "passive"))
    )
    (net (code "27") (name "Net-(D1-PadA)") (class "Default")
      (node (ref "D1") (pin "A") (pinfunction "A_A") (pintype "passive"))
      (node (ref "R15") (pin "2") (pinfunction "2_2") (pintype "passive"))
    )
    (net (code "28") (name "Net-(D2-PadA)") (class "Default")
      (node (ref "D2") (pin "A") (pinfunction "A_A") (pintype "passive"))
      (node (ref "R16") (pin "1") (pinfunction "1_1") (pintype "passive"))
    )
    (net (code "29") (name "Net-(D3-PadA)") (class "Default")
      (node (ref "D3") (pin "A") (pinfunction "A_A") (pintype "passive"))
      (node (ref "R59") (pin "2") (pinfunction "2_2") (pintype "passive"))
    )
    (net (code "30") (name "Net-(D4-K)") (class "Default")
      (node (ref "C24") (pin "2") (pinfunction "2_2") (pintype "passive"))
      (node (ref "C80") (pin "2") (pinfunction "2_2") (pintype "passive"))
      (node (ref "D4") (pin "C") (pinfunction "K_C") (pintype "passive"))
      (node (ref "U5") (pin "16") (pinfunction "VDDA_16") (pintype "passive"))
    )
    (net (code "31") (name "Net-(D4-PadA)") (class "Default")
      (node (ref "D4") (pin "A") (pinfunction "A_A") (pintype "passive"))
      (node (ref "R27") (pin "2") (pinfunction "2_2") (pintype "passive"))
    )
    (net (code "32") (name "Net-(D5-PadA)") (class "Default")
      (node (ref "D5") (pin "A") (pinfunction "A_A") (pintype "passive"))
      (node (ref "R60") (pin "1") (pinfunction "1_1") (pintype "passive"))
    )
    (net (code "33") (name "Net-(D6-PadA)") (class "Default")
      (node (ref "D6") (pin "A") (pinfunction "A_A") (pintype "passive"))
      (node (ref "R38") (pin "2") (pinfunction "2_2") (pintype "passive"))
    )
    (net (code "34") (name "Net-(D7-K)") (class "Default")
      (node (ref "C33") (pin "2") (pinfunction "2_2") (pintype "passive"))
      (node (ref "C34") (pin "2") (pinfunction "2_2") (pintype "passive"))
      (node (ref "D7") (pin "C") (pinfunction "K_C") (pintype "passive"))
      (node (ref "U6") (pin "16") (pinfunction "VDDA_16") (pintype "passive"))
    )
    (net (code "35") (name "Net-(D7-PadA)") (class "Default")
      (node (ref "D7") (pin "A") (pinfunction "A_A") (pintype "passive"))
      (node (ref "R39") (pin "2") (pinfunction "2_2") (pintype "passive"))
    )
    (net (code "36") (name "Net-(D8-PadA)") (class "Default")
      (node (ref "D8") (pin "A") (pinfunction "A_A") (pintype "passive"))
      (node (ref "R40") (pin "1") (pinfunction "1_1") (pintype "passive"))
    )
    (net (code "37") (name "Net-(D9-PadA)") (class "Default")
      (node (ref "D9") (pin "A") (pinfunction "A_A") (pintype "passive"))
      (node (ref "R50") (pin "2") (pinfunction "2_2") (pintype "passive"))
    )
    (net (code "38") (name "Net-(U4-DISABLE)") (class "Default")
      (node (ref "C15") (pin "1") (pinfunction "1_1") (pintype "passive"))
      (node (ref "R18") (pin "1") (pinfunction "1_1") (pintype "passive"))
      (node (ref "R23") (pin "2") (pinfunction "2_2") (pintype "passive"))
      (node (ref "U4") (pin "5") (pinfunction "DISABLE_5") (pintype "passive"))
    )
    (net (code "39") (name "Net-(U4-DT)") (class "Default")
      (node (ref "C18") (pin "2") (pinfunction "2_2") (pintype "passive"))
      (node (ref "R24") (pin "2") (pinfunction "2_2") (pintype "passive"))
      (node (ref "U4") (pin "6") (pinfunction "DT_6") (pintype "passive"))
    )
    (net (code "40") (name "Net-(U4-INA)") (class "Default")
      (node (ref "C17") (pin "1") (pinfunction "1_1") (pintype "passive"))
      (node (ref "R20") (pin "1") (pinfunction "1_1") (pintype "passive"))
      (node (ref "R21") (pin "2") (pinfunction "2_2") (pintype "passive"))
      (node (ref "U4") (pin "1") (pinfunction "INA_1") (pintype "passive"))
    )
    (net (code "41") (name "Net-(U4-INB)") (class "Default")
      (node (ref "C16") (pin "1") (pinfunction "1_1") (pintype "passive"))
      (node (ref "R19") (pin "1") (pinfunction "1_1") (pintype "passive"))
      (node (ref "R22") (pin "2") (pinfunction "2_2") (pintype "passive"))
      (node (ref "U4") (pin "2") (pinfunction "INB_2") (pintype "passive"))
    )
    (net (code "42") (name "Net-(U4-OUTA)") (class "Default")
      (node (ref "D2") (pin "C") (pinfunction "C_C") (pintype "passive"))
      (node (ref "R17") (pin "1") (pinfunction "1_1") (pintype "passive"))
      (node (ref "U4") (pin "15") (pinfunction "OUTA_15") (pintype "passive"))
    )
    (net (code "43") (name "Net-(U4-OUTB)") (class "Default")
      (node (ref "D3") (pin "C") (pinfunction "C_C") (pintype "passive"))
      (node (ref "R58") (pin "2") (pinfunction "2_2") (pintype "passive"))
      (node (ref "U4") (pin "10") (pinfunction "OUTB_10") (pintype "passive"))
    )
    (net (code "44") (name "Net-(U5-DISABLE)") (class "Default")
      (node (ref "C25") (pin "1") (pinfunction "1_1") (pintype "passive"))
      (node (ref "R30") (pin "1") (pinfunction "1_1") (pintype "passive"))
      (node (ref "R62") (pin "2") (pinfunction "2_2") (pintype "passive"))
      (node (ref "U5") (pin "5") (pinfunction "DISABLE_5") (pintype "passive"))
    )
    (net (code "45") (name "Net-(U5-DT)") (class "Default")
      (node (ref "C95") (pin "2") (pinfunction "2_2") (pintype "passive"))
      (node (ref "R36") (pin "2") (pinfunction "2_2") (pintype "passive"))
      (node (ref "U5") (pin "6") (pinfunction "DT_6") (pintype "passive"))
    )
    (net (code "46") (name "Net-(U5-INA)") (class "Default")
      (node (ref "C83") (pin "1") (pinfunction "1_1") (pintype "passive"))
      (node (ref "R32") (pin "1") (pinfunction "1_1") (pintype "passive"))
      (node (ref "R61") (pin "2") (pinfunction "2_2") (pintype "passive"))
      (node (ref "U5") (pin "1") (pinfunction "INA_1") (pintype "passive"))
    )
    (net (code "47") (name "Net-(U5-INB)") (class "Default")
      (node (ref "C26") (pin "1") (pinfunction "1_1") (pintype "passive"))
      (node (ref "R31") (pin "1") (pinfunction "1_1") (pintype "passive"))
      (node (ref "R34") (pin "2") (pinfunction "2_2") (pintype "passive"))
      (node (ref "U5") (pin "2") (pinfunction "INB_2") (pintype "passive"))
    )
    (net (code "48") (name "Net-(U5-OUTA)") (class "Default")
      (node (ref "D5") (pin "C") (pinfunction "C_C") (pintype "passive"))
      (node (ref "R29") (pin "1") (pinfunction "1_1") (pintype "passive"))
      (node (ref "U5") (pin "15") (pinfunction "OUTA_15") (pintype "passive"))
    )
    (net (code "49") (name "Net-(U5-OUTB)") (class "Default")
      (node (ref "D6") (pin "C") (pinfunction "C_C") (pintype "passive"))
      (node (ref "R37") (pin "2") (pinfunction "2_2") (pintype "passive"))
      (node (ref "U5") (pin "10") (pinfunction "OUTB_10") (pintype "passive"))
    )
    (net (code "50") (name "Net-(U6-DISABLE)") (class "Default")
      (node (ref "C35") (pin "1") (pinfunction "1_1") (pintype "passive"))
      (node (ref "R42") (pin "1") (pinfunction "1_1") (pintype "passive"))
      (node (ref "R64") (pin "2") (pinfunction "2_2") (pintype "passive"))
      (node (ref "U6") (pin "5") (pinfunction "DISABLE_5") (pintype "passive"))
    )
    (net (code "51") (name "Net-(U6-DT)") (class "Default")
      (node (ref "C38") (pin "2") (pinfunction "2_2") (pintype "passive"))
      (node (ref "R48") (pin "2") (pinfunction "2_2") (pintype "passive"))
      (node (ref "U6") (pin "6") (pinfunction "DT_6") (pintype "passive"))
    )
    (net (code "52") (name "Net-(U6-INA)") (class "Default")
      (node (ref "C37") (pin "1") (pinfunction "1_1") (pintype "passive"))
      (node (ref "R44") (pin "1") (pinfunction "1_1") (pintype "passive"))
      (node (ref "R45") (pin "2") (pinfunction "2_2") (pintype "passive"))
      (node (ref "U6") (pin "1") (pinfunction "INA_1") (pintype "passive"))
    )
    (net (code "53") (name "Net-(U6-INB)") (class "Default")
      (node (ref "C36") (pin "1") (pinfunction "1_1") (pintype "passive"))
      (node (ref "R43") (pin "1") (pinfunction "1_1") (pintype "passive"))
      (node (ref "R63") (pin "2") (pinfunction "2_2") (pintype "passive"))
      (node (ref "U6") (pin "2") (pinfunction "INB_2") (pintype "passive"))
    )
    (net (code "54") (name "Net-(U6-OUTA)") (class "Default")
      (node (ref "D8") (pin "C") (pinfunction "C_C") (pintype "passive"))
      (node (ref "R41") (pin "1") (pinfunction "1_1") (pintype "passive"))
      (node (ref "U6") (pin "15") (pinfunction "OUTA_15") (pintype "passive"))
    )
    (net (code "55") (name "Net-(U6-OUTB)") (class "Default")
      (node (ref "D9") (pin "C") (pinfunction "C_C") (pintype "passive"))
      (node (ref "R65") (pin "2") (pinfunction "2_2") (pintype "passive"))
      (node (ref "U6") (pin "10") (pinfunction "OUTB_10") (pintype "passive"))
    )
    (net (code "56") (name "VIN+") (class "Default")
      (node (ref "J24") (pin "1") (pinfunction "1_1") (pintype "passive"))
      (node (ref "J24") (pin "2") (pinfunction "2_2") (pintype "passive"))
      (node (ref "J24") (pin "3") (pinfunction "3_3") (pintype "passive"))
      (node (ref "J24") (pin "4") (pinfunction "4_4") (pintype "passive"))
      (node (ref "J24") (pin "5") (pinfunction "5_5") (pintype "passive"))
      (node (ref "J24") (pin "6") (pinfunction "6_6") (pintype "passive"))
    )
    (net (code "57") (name "unconnected-(U4-NC_1-Pad7)") (class "Default")
      (node (ref "U4") (pin "7") (pinfunction "NC_1_7") (pintype "passive"))
    )
    (net (code "58") (name "unconnected-(U4-NC_2-Pad12)") (class "Default")
      (node (ref "U4") (pin "12") (pinfunction "NC_2_12") (pintype "passive"))
    )
    (net (code "59") (name "unconnected-(U4-NC_3-Pad13)") (class "Default")
      (node (ref "U4") (pin "13") (pinfunction "NC_3_13") (pintype "passive"))
    )
    (net (code "60") (name "unconnected-(U5-NC_1-Pad7)") (class "Default")
      (node (ref "U5") (pin "7") (pinfunction "NC_1_7") (pintype "passive"))
    )
    (net (code "61") (name "unconnected-(U5-NC_2-Pad12)") (class "Default")
      (node (ref "U5") (pin "12") (pinfunction "NC_2_12") (pintype "passive"))
    )
    (net (code "62") (name "unconnected-(U5-NC_3-Pad13)") (class "Default")
      (node (ref "U5") (pin "13") (pinfunction "NC_3_13") (pintype "passive"))
    )
    (net (code "63") (name "unconnected-(U6-NC_1-Pad7)") (class "Default")
      (node (ref "U6") (pin "7") (pinfunction "NC_1_7") (pintype "passive"))
    )
    (net (code "64") (name "unconnected-(U6-NC_2-Pad12)") (class "Default")
      (node (ref "U6") (pin "12") (pinfunction "NC_2_12") (pintype "passive"))
    )
    (net (code "65") (name "unconnected-(U6-NC_3-Pad13)") (class "Default")
      (node (ref "U6") (pin "13") (pinfunction "NC_3_13") (pintype "passive"))
    )
  )
)
